# AutoISP84.net
KiCad netlist of a schematic drawn in EAGLE
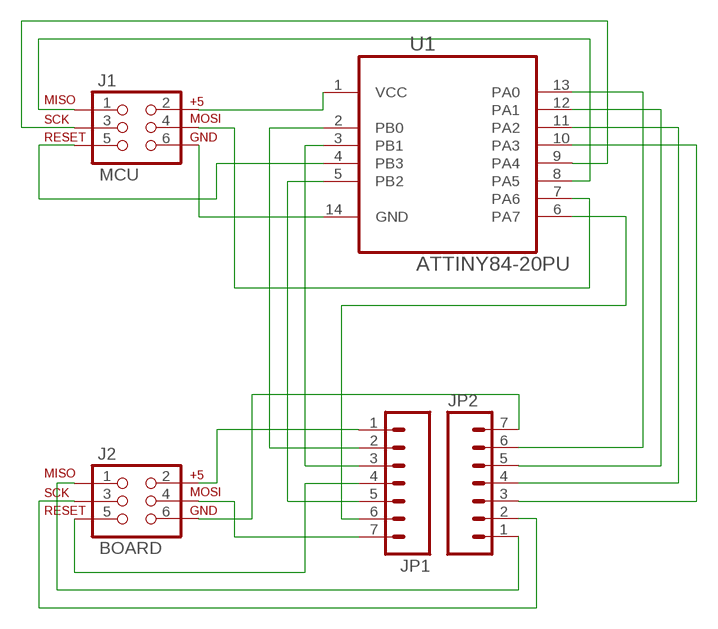
[diagram p0: schematic, sheet 1]

(export (version "E")
  (design (tool "Eeschema 10.0.6"))
  (components
    (comp (ref "J1")
      (value "MCU")
      (footprint "eagle-import:2X3")
      (libsource (lib "eagle-import") (part "AVR_SPI_PRG_6PTH"))
    )
    (comp (ref "J2")
      (value "BOARD")
      (footprint "eagle-import:2X3")
      (libsource (lib "eagle-import") (part "AVR_SPI_PRG_6PTH"))
    )
    (comp (ref "JP1")
      (value "M07")
      (footprint "eagle-import:1X07")
      (libsource (lib "eagle-import") (part "M07"))
    )
    (comp (ref "JP2")
      (value "M07")
      (footprint "eagle-import:1X07")
      (libsource (lib "eagle-import") (part "M07"))
    )
    (comp (ref "U1")
      (value "ATTINY84-20PU")
      (footprint "eagle-import:DIP254P762X533-14")
      (libsource (lib "eagle-import") (part "ATTINY84-20PU"))
    )
  )
  (nets
    (net (code "1") (name "Net-(J2-Pad1)") (class "Default")
      (node (ref "J2") (pin "1") (pinfunction "1_1") (pintype "passive"))
      (node (ref "JP2") (pin "1") (pinfunction "1_1") (pintype "passive"))
    )
    (net (code "2") (name "Net-(J2-Pad2)") (class "Default")
      (node (ref "J2") (pin "2") (pinfunction "2_2") (pintype "passive"))
      (node (ref "JP1") (pin "1") (pinfunction "1_1") (pintype "passive"))
    )
    (net (code "3") (name "Net-(J2-Pad3)") (class "Default")
      (node (ref "J2") (pin "3") (pinfunction "3_3") (pintype "passive"))
      (node (ref "JP2") (pin "2") (pinfunction "2_2") (pintype "passive"))
    )
    (net (code "4") (name "Net-(J2-Pad4)") (class "Default")
      (node (ref "J2") (pin "4") (pinfunction "4_4") (pintype "passive"))
      (node (ref "JP1") (pin "7") (pinfunction "7_7") (pintype "passive"))
    )
    (net (code "5") (name "Net-(J2-Pad5)") (class "Default")
      (node (ref "J2") (pin "5") (pinfunction "5_5") (pintype "passive"))
      (node (ref "JP1") (pin "4") (pinfunction "4_4") (pintype "passive"))
    )
    (net (code "6") (name "Net-(J2-Pad6)") (class "Default")
      (node (ref "J2") (pin "6") (pinfunction "6_6") (pintype "passive"))
      (node (ref "JP2") (pin "7") (pinfunction "7_7") (pintype "passive"))
    )
    (net (code "7") (name "Net-(U1-GND)") (class "Default")
      (node (ref "J1") (pin "6") (pinfunction "6_6") (pintype "passive"))
      (node (ref "U1") (pin "14") (pinfunction "GND_14") (pintype "passive"))
    )
    (net (code "8") (name "Net-(U1-PA0)") (class "Default")
      (node (ref "JP2") (pin "6") (pinfunction "6_6") (pintype "passive"))
      (node (ref "U1") (pin "13") (pinfunction "PA0_13") (pintype "bidirectional"))
    )
    (net (code "9") (name "Net-(U1-PA1)") (class "Default")
      (node (ref "JP2") (pin "5") (pinfunction "5_5") (pintype "passive"))
      (node (ref "U1") (pin "12") (pinfunction "PA1_12") (pintype "bidirectional"))
    )
    (net (code "10") (name "Net-(U1-PA2)") (class "Default")
      (node (ref "JP2") (pin "4") (pinfunction "4_4") (pintype "passive"))
      (node (ref "U1") (pin "11") (pinfunction "PA2_11") (pintype "bidirectional"))
    )
    (net (code "11") (name "Net-(U1-PA3)") (class "Default")
      (node (ref "JP2") (pin "3") (pinfunction "3_3") (pintype "passive"))
      (node (ref "U1") (pin "10") (pinfunction "PA3_10") (pintype "bidirectional"))
    )
    (net (code "12") (name "Net-(U1-PA4)") (class "Default")
      (node (ref "J1") (pin "3") (pinfunction "3_3") (pintype "passive"))
      (node (ref "U1") (pin "9") (pinfunction "PA4_9") (pintype "bidirectional"))
    )
    (net (code "13") (name "Net-(U1-PA5)") (class "Default")
      (node (ref "J1") (pin "1") (pinfunction "1_1") (pintype "passive"))
      (node (ref "U1") (pin "8") (pinfunction "PA5_8") (pintype "bidirectional"))
    )
    (net (code "14") (name "Net-(U1-PA6)") (class "Default")
      (node (ref "J1") (pin "4") (pinfunction "4_4") (pintype "passive"))
      (node (ref "U1") (pin "7") (pinfunction "PA6_7") (pintype "bidirectional"))
    )
    (net (code "15") (name "Net-(U1-PA7)") (class "Default")
      (node (ref "JP1") (pin "6") (pinfunction "6_6") (pintype "passive"))
      (node (ref "U1") (pin "6") (pinfunction "PA7_6") (pintype "bidirectional"))
    )
    (net (code "16") (name "Net-(U1-PB0)") (class "Default")
      (node (ref "JP1") (pin "2") (pinfunction "2_2") (pintype "passive"))
      (node (ref "U1") (pin "2") (pinfunction "PB0_2") (pintype "bidirectional"))
    )
    (net (code "17") (name "Net-(U1-PB1)") (class "Default")
      (node (ref "JP1") (pin "3") (pinfunction "3_3") (pintype "passive"))
      (node (ref "U1") (pin "3") (pinfunction "PB1_3") (pintype "bidirectional"))
    )
    (net (code "18") (name "Net-(U1-PB2)") (class "Default")
      (node (ref "JP1") (pin "5") (pinfunction "5_5") (pintype "passive"))
      (node (ref "U1") (pin "5") (pinfunction "PB2_5") (pintype "bidirectional"))
    )
    (net (code "19") (name "Net-(U1-PB3)") (class "Default")
      (node (ref "J1") (pin "5") (pinfunction "5_5") (pintype "passive"))
      (node (ref "U1") (pin "4") (pinfunction "PB3_4") (pintype "bidirectional"))
    )
    (net (code "20") (name "Net-(U1-VCC)") (class "Default")
      (node (ref "J1") (pin "2") (pinfunction "2_2") (pintype "passive"))
      (node (ref "U1") (pin "1") (pinfunction "VCC_1") (pintype "power_in"))
    )
  )
)
